# Scheme.net
KiCad netlist of a schematic drawn in EAGLE
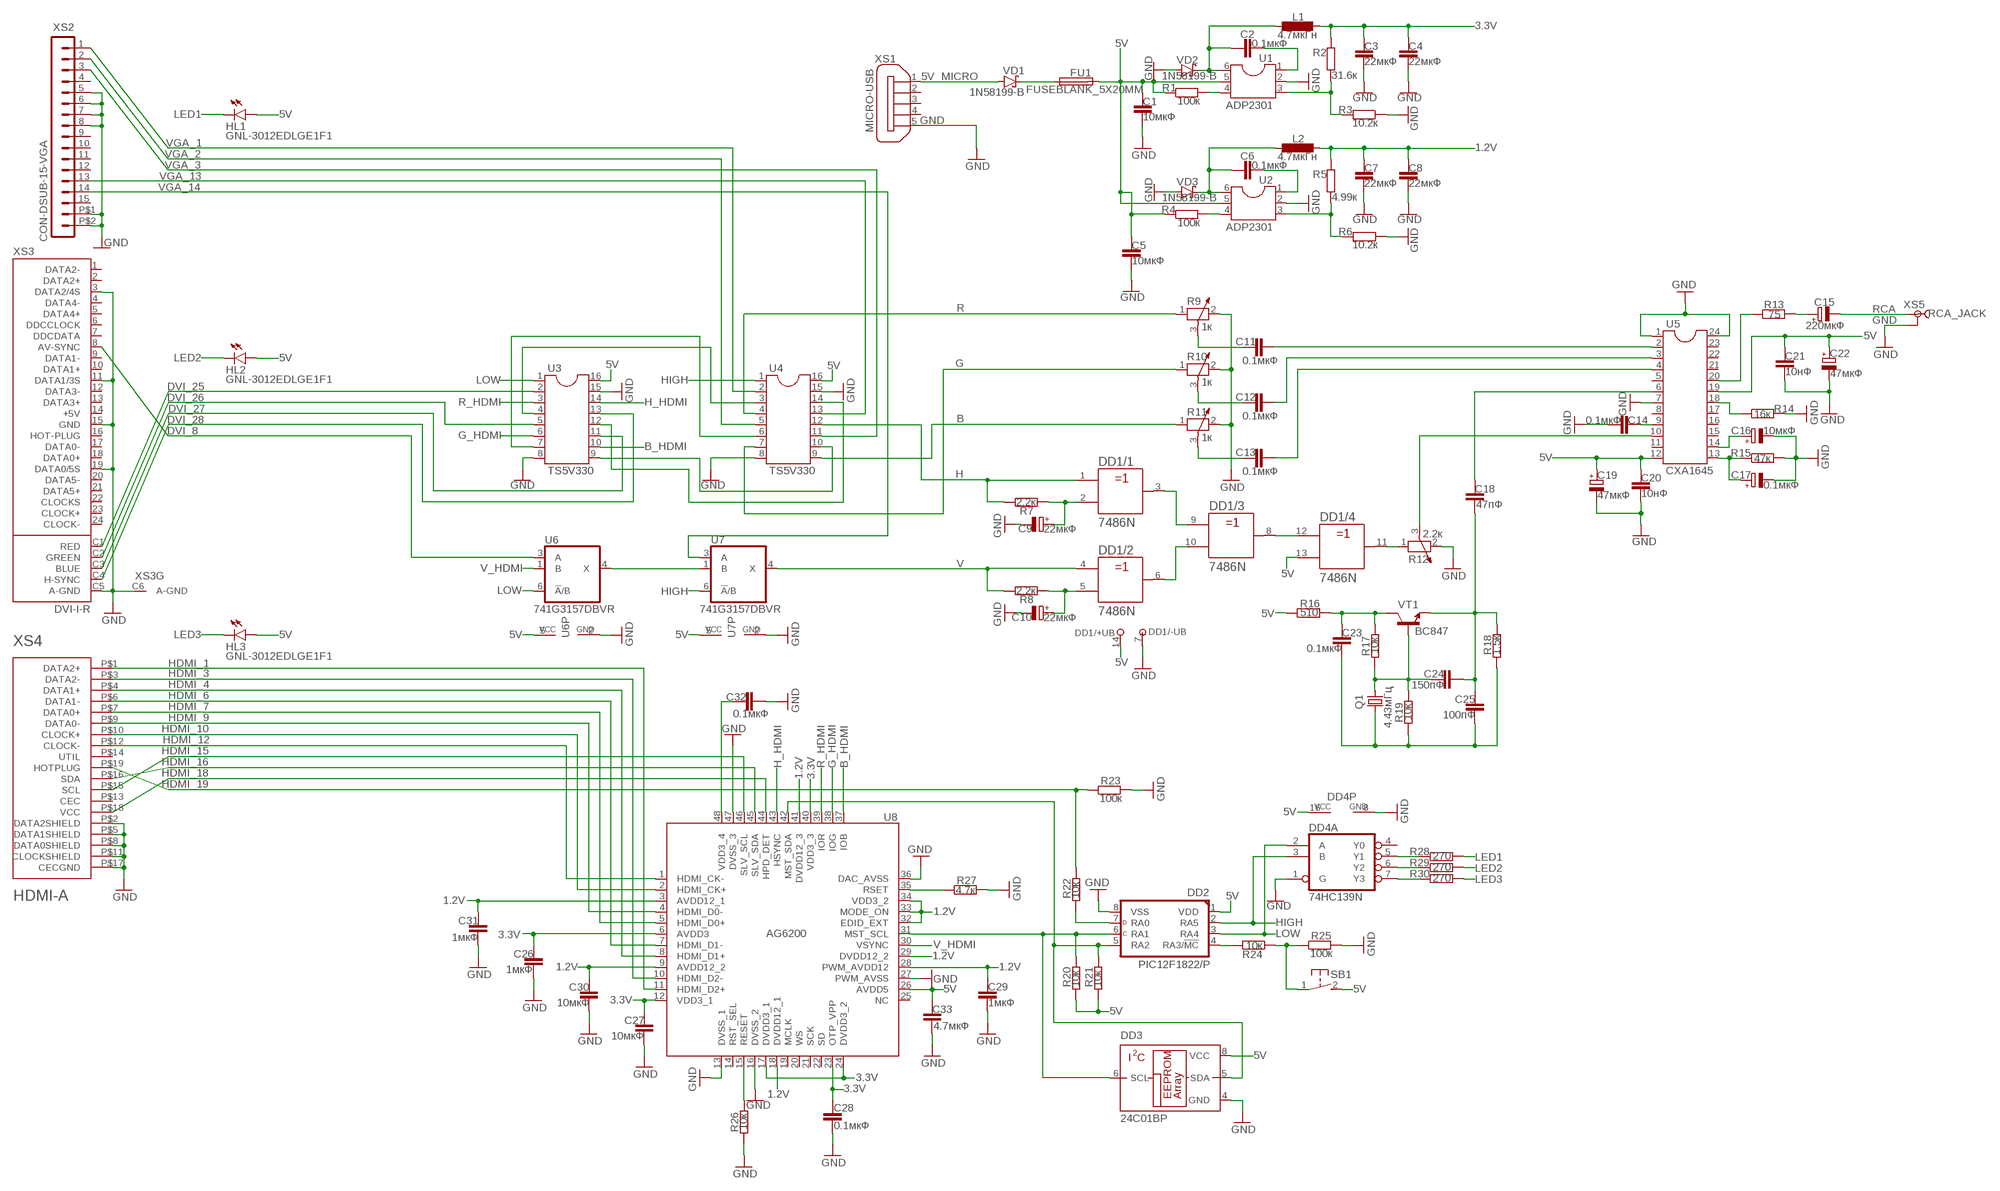
[diagram p0: schematic, sheet 1]

(export (version "E")
  (design (tool "Eeschema 10.0.6"))
  (components
    (comp (ref "C1")
      (value "10мкФ")
      (footprint "eagle-import:C0603")
      (libsource (lib "eagle-import") (part "C-EUC0603"))
    )
    (comp (ref "C2")
      (value "0.1мкФ")
      (footprint "eagle-import:C1206")
      (libsource (lib "eagle-import") (part "C-EUC1206"))
    )
    (comp (ref "C3")
      (value "22мкФ")
      (footprint "eagle-import:C1206")
      (libsource (lib "eagle-import") (part "C-EUC1206"))
    )
    (comp (ref "C4")
      (value "22мкФ")
      (footprint "eagle-import:C1206")
      (libsource (lib "eagle-import") (part "C-EUC1206"))
    )
    (comp (ref "C5")
      (value "10мкФ")
      (footprint "eagle-import:C0603")
      (libsource (lib "eagle-import") (part "C-EUC0603"))
    )
    (comp (ref "C6")
      (value "0.1мкФ")
      (footprint "eagle-import:C1206")
      (libsource (lib "eagle-import") (part "C-EUC1206"))
    )
    (comp (ref "C7")
      (value "22мкФ")
      (footprint "eagle-import:C1206")
      (libsource (lib "eagle-import") (part "C-EUC1206"))
    )
    (comp (ref "C8")
      (value "22мкФ")
      (footprint "eagle-import:C1206")
      (libsource (lib "eagle-import") (part "C-EUC1206"))
    )
    (comp (ref "C9")
      (value "22мкФ")
      (footprint "eagle-import:E2,5-6E")
      (libsource (lib "eagle-import") (part "CPOL-EUE2,5-6E"))
    )
    (comp (ref "C10")
      (value "22мкФ")
      (footprint "eagle-import:E2,5-6E")
      (libsource (lib "eagle-import") (part "CPOL-EUE2,5-6E"))
    )
    (comp (ref "C11")
      (value "0.1мкФ")
      (footprint "eagle-import:C1206")
      (libsource (lib "eagle-import") (part "C-EUC1206"))
    )
    (comp (ref "C12")
      (value "0.1мкФ")
      (footprint "eagle-import:C1206")
      (libsource (lib "eagle-import") (part "C-EUC1206"))
    )
    (comp (ref "C13")
      (value "0.1мкФ")
      (footprint "eagle-import:C1206")
      (libsource (lib "eagle-import") (part "C-EUC1206"))
    )
    (comp (ref "C14")
      (value "0.1мкФ")
      (footprint "eagle-import:C1206")
      (libsource (lib "eagle-import") (part "C-EUC1206"))
    )
    (comp (ref "C15")
      (value "220мкФ")
      (footprint "eagle-import:E2,5-6E")
      (libsource (lib "eagle-import") (part "CPOL-EUE2,5-6E"))
    )
    (comp (ref "C16")
      (value "10мкФ")
      (footprint "eagle-import:E2,5-6E")
      (libsource (lib "eagle-import") (part "CPOL-EUE2,5-6E"))
    )
    (comp (ref "C17")
      (value "0.1мкФ")
      (footprint "eagle-import:E2,5-6E")
      (libsource (lib "eagle-import") (part "CPOL-EUE2,5-6E"))
    )
    (comp (ref "C18")
      (value "47пФ")
      (footprint "eagle-import:C0603")
      (libsource (lib "eagle-import") (part "C-EUC0603"))
    )
    (comp (ref "C19")
      (value "47мкФ")
      (footprint "eagle-import:E2,5-6E")
      (libsource (lib "eagle-import") (part "CPOL-EUE2,5-6E"))
    )
    (comp (ref "C20")
      (value "10нФ")
      (footprint "eagle-import:C0603")
      (libsource (lib "eagle-import") (part "C-EUC0603"))
    )
    (comp (ref "C21")
      (value "10нФ")
      (footprint "eagle-import:C0603")
      (libsource (lib "eagle-import") (part "C-EUC0603"))
    )
    (comp (ref "C22")
      (value "47мкФ")
      (footprint "eagle-import:E2,5-6E")
      (libsource (lib "eagle-import") (part "CPOL-EUE2,5-6E"))
    )
    (comp (ref "C23")
      (value "0.1мкФ")
      (footprint "eagle-import:C1206")
      (libsource (lib "eagle-import") (part "C-EUC1206"))
    )
    (comp (ref "C24")
      (value "150пФ")
      (footprint "eagle-import:C0805")
      (libsource (lib "eagle-import") (part "C-EUC0805"))
    )
    (comp (ref "C25")
      (value "100пФ")
      (footprint "eagle-import:C0805")
      (libsource (lib "eagle-import") (part "C-EUC0805"))
    )
    (comp (ref "C26")
      (value "1мкФ")
      (footprint "eagle-import:C0603")
      (libsource (lib "eagle-import") (part "C-EUC0603"))
    )
    (comp (ref "C27")
      (value "10мкФ")
      (footprint "eagle-import:C0603")
      (libsource (lib "eagle-import") (part "C-EUC0603"))
    )
    (comp (ref "C28")
      (value "0.1мкФ")
      (footprint "eagle-import:C1206")
      (libsource (lib "eagle-import") (part "C-EUC1206"))
    )
    (comp (ref "C29")
      (value "1мкФ")
      (footprint "eagle-import:C0603")
      (libsource (lib "eagle-import") (part "C-EUC0603"))
    )
    (comp (ref "C30")
      (value "10мкФ")
      (footprint "eagle-import:C0603")
      (libsource (lib "eagle-import") (part "C-EUC0603"))
    )
    (comp (ref "C31")
      (value "1мкФ")
      (footprint "eagle-import:C0603")
      (libsource (lib "eagle-import") (part "C-EUC0603"))
    )
    (comp (ref "C32")
      (value "0.1мкФ")
      (footprint "eagle-import:C1206")
      (libsource (lib "eagle-import") (part "C-EUC1206"))
    )
    (comp (ref "C33")
      (value "4.7мкФ")
      (footprint "eagle-import:C0805")
      (libsource (lib "eagle-import") (part "C-EUC0805"))
    )
    (comp (ref "DD1")
      (value "7486N")
      (footprint "eagle-import:DIL14")
      (libsource (lib "eagle-import") (part "7486N"))
    )
    (comp (ref "DD2")
      (value "PIC12F1822/P")
      (footprint "eagle-import:DIL8-P")
      (libsource (lib "eagle-import") (part "PIC12F1822/P"))
    )
    (comp (ref "DD3")
      (value "24C01BP")
      (footprint "eagle-import:DIL8")
      (fields (field (name "MPN") "AT24C01B-PU"))
      (libsource (lib "eagle-import") (part "24C0P1B"))
    )
    (comp (ref "DD4")
      (value "74HC139N")
      (footprint "eagle-import:DIL16")
      (libsource (lib "eagle-import") (part "74139NHC"))
    )
    (comp (ref "FU1")
      (value "FUSEBLANK_5X20MM")
      (footprint "eagle-import:FUSE_HOLDER_5X20MM")
      (libsource (lib "eagle-import") (part "FUSEBLANK_5X20MM"))
    )
    (comp (ref "HL1")
      (value "GNL-3012EDLGE1F1")
      (footprint "eagle-import:PLCC2")
      (libsource (lib "eagle-import") (part "GNL-3012EDE1F1LG"))
    )
    (comp (ref "HL2")
      (value "GNL-3012EDLGE1F1")
      (footprint "eagle-import:PLCC2")
      (libsource (lib "eagle-import") (part "GNL-3012EDE1F1LG"))
    )
    (comp (ref "HL3")
      (value "GNL-3012EDLGE1F1")
      (footprint "eagle-import:PLCC2")
      (libsource (lib "eagle-import") (part "GNL-3012EDE1F1LG"))
    )
    (comp (ref "L1")
      (value "4.7мкГн")
      (footprint "eagle-import:PIS2816")
      (libsource (lib "eagle-import") (part "L-EUPIS2816"))
    )
    (comp (ref "L2")
      (value "4.7мкГн")
      (footprint "eagle-import:PIS2816")
      (libsource (lib "eagle-import") (part "L-EUPIS2816"))
    )
    (comp (ref "Q1")
      (value "4.43мГц")
      (footprint "eagle-import:HC49U-V")
      (libsource (lib "eagle-import") (part "CRYSTALHC49U-V"))
    )
    (comp (ref "R1")
      (value "100к")
      (footprint "eagle-import:R2512")
      (libsource (lib "eagle-import") (part "R-EU_R2512"))
    )
    (comp (ref "R2")
      (value "31.6к")
      (footprint "eagle-import:R0805")
      (libsource (lib "eagle-import") (part "R-EU_R0805"))
    )
    (comp (ref "R3")
      (value "10.2к")
      (footprint "eagle-import:R0805")
      (libsource (lib "eagle-import") (part "R-EU_R0805"))
    )
    (comp (ref "R4")
      (value "100к")
      (footprint "eagle-import:R2512")
      (libsource (lib "eagle-import") (part "R-EU_R2512"))
    )
    (comp (ref "R5")
      (value "4.99к")
      (footprint "eagle-import:R0805")
      (libsource (lib "eagle-import") (part "R-EU_R0805"))
    )
    (comp (ref "R6")
      (value "10.2к")
      (footprint "eagle-import:R0805")
      (libsource (lib "eagle-import") (part "R-EU_R0805"))
    )
    (comp (ref "R7")
      (value "2.2к")
      (footprint "eagle-import:R0402")
      (libsource (lib "eagle-import") (part "R-EU_R0402"))
    )
    (comp (ref "R8")
      (value "2.2к")
      (footprint "eagle-import:R0402")
      (libsource (lib "eagle-import") (part "R-EU_R0402"))
    )
    (comp (ref "R9")
      (value "1к")
      (footprint "eagle-import:PT-10")
      (libsource (lib "eagle-import") (part "POTENTIOMETER_PT-10"))
    )
    (comp (ref "R10")
      (value "1к")
      (footprint "eagle-import:PT-10")
      (libsource (lib "eagle-import") (part "POTENTIOMETER_PT-10"))
    )
    (comp (ref "R11")
      (value "1к")
      (footprint "eagle-import:PT-10")
      (libsource (lib "eagle-import") (part "POTENTIOMETER_PT-10"))
    )
    (comp (ref "R12")
      (value "2.2к")
      (footprint "eagle-import:PT-10")
      (libsource (lib "eagle-import") (part "POTENTIOMETER_PT-10"))
    )
    (comp (ref "R13")
      (value "75")
      (footprint "eagle-import:R0402")
      (libsource (lib "eagle-import") (part "R-EU_R0402"))
    )
    (comp (ref "R14")
      (value "16к")
      (footprint "eagle-import:R0402")
      (libsource (lib "eagle-import") (part "R-EU_R0402"))
    )
    (comp (ref "R15")
      (value "47к")
      (footprint "eagle-import:R0402")
      (libsource (lib "eagle-import") (part "R-EU_R0402"))
    )
    (comp (ref "R16")
      (value "510")
      (footprint "eagle-import:R0402")
      (libsource (lib "eagle-import") (part "R-EU_R0402"))
    )
    (comp (ref "R17")
      (value "10к")
      (footprint "eagle-import:R0805")
      (libsource (lib "eagle-import") (part "R-EU_R0805"))
    )
    (comp (ref "R18")
      (value "1.5к")
      (footprint "eagle-import:R0402")
      (libsource (lib "eagle-import") (part "R-EU_R0402"))
    )
    (comp (ref "R19")
      (value "10к")
      (footprint "eagle-import:R0805")
      (libsource (lib "eagle-import") (part "R-EU_R0805"))
    )
    (comp (ref "R20")
      (value "10к")
      (footprint "eagle-import:R0805")
      (libsource (lib "eagle-import") (part "R-EU_R0805"))
    )
    (comp (ref "R21")
      (value "10к")
      (footprint "eagle-import:R0805")
      (libsource (lib "eagle-import") (part "R-EU_R0805"))
    )
    (comp (ref "R22")
      (value "10к")
      (footprint "eagle-import:R0805")
      (libsource (lib "eagle-import") (part "R-EU_R0805"))
    )
    (comp (ref "R23")
      (value "100к")
      (footprint "eagle-import:R2512")
      (libsource (lib "eagle-import") (part "R-EU_R2512"))
    )
    (comp (ref "R24")
      (value "10к")
      (footprint "eagle-import:R0805")
      (libsource (lib "eagle-import") (part "R-EU_R0805"))
    )
    (comp (ref "R25")
      (value "100к")
      (footprint "eagle-import:R2512")
      (libsource (lib "eagle-import") (part "R-EU_R2512"))
    )
    (comp (ref "R26")
      (value "10к")
      (footprint "eagle-import:R0805")
      (libsource (lib "eagle-import") (part "R-EU_R0805"))
    )
    (comp (ref "R27")
      (value "4.7к")
      (footprint "eagle-import:R0402")
      (libsource (lib "eagle-import") (part "R-EU_R0402"))
    )
    (comp (ref "R28")
      (value "270")
      (footprint "eagle-import:R0402")
      (libsource (lib "eagle-import") (part "R-EU_R0402"))
    )
    (comp (ref "R29")
      (value "270")
      (footprint "eagle-import:R0402")
      (libsource (lib "eagle-import") (part "R-EU_R0402"))
    )
    (comp (ref "R30")
      (value "270")
      (footprint "eagle-import:R0402")
      (libsource (lib "eagle-import") (part "R-EU_R0402"))
    )
    (comp (ref "SB1")
      (value "31-XX")
      (footprint "eagle-import:B3F-31XX")
      (fields (field (name "MPN") "B3F-3100"))
      (libsource (lib "eagle-import") (part "31-XX"))
    )
    (comp (ref "U1")
      (value "ADP2301")
      (footprint "eagle-import:DIL06")
      (libsource (lib "eagle-import") (part "DIL6"))
    )
    (comp (ref "U2")
      (value "ADP2301")
      (footprint "eagle-import:DIL06")
      (libsource (lib "eagle-import") (part "DIL6"))
    )
    (comp (ref "U3")
      (value "TS5V330")
      (footprint "eagle-import:DIL16")
      (libsource (lib "eagle-import") (part "DIL16"))
    )
    (comp (ref "U4")
      (value "TS5V330")
      (footprint "eagle-import:DIL16")
      (libsource (lib "eagle-import") (part "DIL16"))
    )
    (comp (ref "U5")
      (value "CXA1645")
      (footprint "eagle-import:DIL24-4")
      (libsource (lib "eagle-import") (part "DIL24-4"))
    )
    (comp (ref "U6")
      (value "741G3157DBVR")
      (footprint "eagle-import:DBV_R-PDSO-G6")
      (libsource (lib "eagle-import") (part "741G3157DBVR"))
    )
    (comp (ref "U7")
      (value "741G3157DBVR")
      (footprint "eagle-import:DBV_R-PDSO-G6")
      (libsource (lib "eagle-import") (part "741G3157DBVR"))
    )
    (comp (ref "U8")
      (value "AG6200")
      (footprint "eagle-import:PLCC-48")
      (fields (field (name "MPN") "AD1953YSTZRL7"))
      (libsource (lib "eagle-import") (part "AG6200"))
    )
    (comp (ref "VD1")
      (value "1N58199-B")
      (footprint "eagle-import:DO41-7.6")
      (libsource (lib "eagle-import") (part "1N58199-B"))
    )
    (comp (ref "VD2")
      (value "1N58199-B")
      (footprint "eagle-import:DO41-7.6")
      (libsource (lib "eagle-import") (part "1N58199-B"))
    )
    (comp (ref "VD3")
      (value "1N58199-B")
      (footprint "eagle-import:DO41-7.6")
      (libsource (lib "eagle-import") (part "1N58199-B"))
    )
    (comp (ref "VT1")
      (value "BC847")
      (footprint "eagle-import:SOT23-BEC")
      (libsource (lib "eagle-import") (part "-NPN-SOT23-BECBC847"))
    )
    (comp (ref "XS1")
      (value "MICRO-USB")
      (footprint "eagle-import:ZX62D-B-5PA8")
      (fields (field (name "MF") "Hirose") (field (name "MPN") "ZX62D-B-5PA8"))
      (libsource (lib "eagle-import") (part "MICRO-USB"))
    )
    (comp (ref "XS2")
      (value "CON-DSUB-15-VGA")
      (footprint "eagle-import:181-015-212-171")
      (libsource (lib "eagle-import") (part "CON-DSUB-15-VGA"))
    )
    (comp (ref "XS3")
      (value "DVI-I-R")
      (footprint "eagle-import:DVI-I-R")
      (libsource (lib "eagle-import") (part "DVI-I-R"))
    )
    (comp (ref "XS4")
      (value "HDMI-A")
      (footprint "eagle-import:HDMI_A")
      (libsource (lib "eagle-import") (part "HDMI-A"))
    )
    (comp (ref "XS5")
      (value "RCA_JACK")
      (footprint "eagle-import:TOBU3")
      (fields (field (name "MF") "FARNELL") (field (name "MPN") "TOBU 3"))
      (libsource (lib "eagle-import") (part "RCA_JACK"))
    )
  )
  (nets
    (net (code "1") (name "/+5V") (class "Default")
      (node (ref "XS3") (pin "14") (pinfunction "+5V_14") (pintype "power_in"))
    )
    (net (code "2") (name "/1.2V") (class "Default")
      (node (ref "C29") (pin "1") (pinfunction "1_1") (pintype "passive"))
      (node (ref "C30") (pin "1") (pinfunction "1_1") (pintype "passive"))
      (node (ref "C31") (pin "1") (pinfunction "1_1") (pintype "passive"))
      (node (ref "C7") (pin "1") (pinfunction "1_1") (pintype "passive"))
      (node (ref "C8") (pin "1") (pinfunction "1_1") (pintype "passive"))
      (node (ref "L2") (pin "2") (pinfunction "2_2") (pintype "passive"))
      (node (ref "R5") (pin "2") (pinfunction "2_2") (pintype "passive"))
      (node (ref "U8") (pin "18") (pinfunction "DVDD12_1_18") (pintype "power_in"))
      (node (ref "U8") (pin "28") (pinfunction "PWM_AVDD12_28") (pintype "power_in"))
      (node (ref "U8") (pin "29") (pinfunction "DVDD12_2_29") (pintype "power_in"))
      (node (ref "U8") (pin "3") (pinfunction "AVDD12_1_3") (pintype "power_in"))
      (node (ref "U8") (pin "32") (pinfunction "EDID_EXT_32") (pintype "input"))
      (node (ref "U8") (pin "33") (pinfunction "MODE_ON_33") (pintype "input"))
      (node (ref "U8") (pin "34") (pinfunction "VDD3_2_34") (pintype "power_in"))
      (node (ref "U8") (pin "41") (pinfunction "DVDD12_3_41") (pintype "power_in"))
      (node (ref "U8") (pin "9") (pinfunction "AVDD12_2_9") (pintype "power_in"))
    )
    (net (code "3") (name "/3.3V") (class "Default")
      (node (ref "C26") (pin "1") (pinfunction "1_1") (pintype "passive"))
      (node (ref "C27") (pin "1") (pinfunction "1_1") (pintype "passive"))
      (node (ref "C28") (pin "1") (pinfunction "1_1") (pintype "passive"))
      (node (ref "C3") (pin "1") (pinfunction "1_1") (pintype "passive"))
      (node (ref "C4") (pin "1") (pinfunction "1_1") (pintype "passive"))
      (node (ref "L1") (pin "2") (pinfunction "2_2") (pintype "passive"))
      (node (ref "R2") (pin "2") (pinfunction "2_2") (pintype "passive"))
      (node (ref "U8") (pin "12") (pinfunction "VDD3_1_12") (pintype "power_in"))
      (node (ref "U8") (pin "17") (pinfunction "DVDD3_1_17") (pintype "power_in"))
      (node (ref "U8") (pin "23") (pinfunction "OTP_VPP_23") (pintype "power_in"))
      (node (ref "U8") (pin "24") (pinfunction "DVDD3_2_24") (pintype "power_in"))
      (node (ref "U8") (pin "40") (pinfunction "VDD3_3_40") (pintype "power_in"))
      (node (ref "U8") (pin "6") (pinfunction "AVDD3_6") (pintype "power_in"))
    )
    (net (code "4") (name "/5V") (class "Default")
      (node (ref "C1") (pin "1") (pinfunction "1_1") (pintype "passive"))
      (node (ref "C19") (pin "+") (pinfunction "+_+") (pintype "passive"))
      (node (ref "C20") (pin "1") (pinfunction "1_1") (pintype "passive"))
      (node (ref "C21") (pin "1") (pinfunction "1_1") (pintype "passive"))
      (node (ref "C22") (pin "+") (pinfunction "+_+") (pintype "passive"))
      (node (ref "C33") (pin "1") (pinfunction "1_1") (pintype "passive"))
      (node (ref "C5") (pin "1") (pinfunction "1_1") (pintype "passive"))
      (node (ref "DD1") (pin "13") (pinfunction "B_13") (pintype "input"))
      (node (ref "DD1") (pin "14") (pinfunction "+UB_14") (pintype "power_in"))
      (node (ref "DD2") (pin "1") (pinfunction "VDD_1") (pintype "passive"))
      (node (ref "DD3") (pin "8") (pinfunction "VCC_8") (pintype "power_in"))
      (node (ref "DD4") (pin "16") (pinfunction "VCC_16") (pintype "power_in"))
      (node (ref "FU1") (pin "2") (pinfunction "2_2") (pintype "passive"))
      (node (ref "HL1") (pin "A") (pinfunction "A_A") (pintype "passive"))
      (node (ref "HL2") (pin "A") (pinfunction "A_A") (pintype "passive"))
      (node (ref "HL3") (pin "A") (pinfunction "A_A") (pintype "passive"))
      (node (ref "R1") (pin "1") (pinfunction "1_1") (pintype "passive"))
      (node (ref "R16") (pin "1") (pinfunction "1_1") (pintype "passive"))
      (node (ref "R20") (pin "1") (pinfunction "1_1") (pintype "passive"))
      (node (ref "R21") (pin "1") (pinfunction "1_1") (pintype "passive"))
      (node (ref "R4") (pin "1") (pinfunction "1_1") (pintype "passive"))
      (node (ref "SB1") (pin "2") (pinfunction "S_2") (pintype "passive"))
      (node (ref "U1") (pin "5") (pinfunction "5_5") (pintype "passive"))
      (node (ref "U2") (pin "5") (pinfunction "5_5") (pintype "passive"))
      (node (ref "U3") (pin "16") (pinfunction "16_16") (pintype "passive"))
      (node (ref "U4") (pin "16") (pinfunction "16_16") (pintype "passive"))
      (node (ref "U5") (pin "12") (pinfunction "12_12") (pintype "passive"))
      (node (ref "U5") (pin "19") (pinfunction "19_19") (pintype "passive"))
      (node (ref "U6") (pin "5") (pinfunction "VCC_5") (pintype "power_in"))
      (node (ref "U7") (pin "5") (pinfunction "VCC_5") (pintype "power_in"))
      (node (ref "U8") (pin "26") (pinfunction "AVDD5_26") (pintype "power_in"))
    )
    (net (code "5") (name "/5V_MICRO") (class "Default")
      (node (ref "VD1") (pin "A") (pinfunction "A_A") (pintype "passive"))
      (node (ref "XS1") (pin "1") (pinfunction "1_1") (pintype "passive"))
    )
    (net (code "6") (name "/B") (class "Default")
      (node (ref "R11") (pin "1") (pinfunction "1_1") (pintype "passive"))
      (node (ref "U4") (pin "9") (pinfunction "9_9") (pintype "passive"))
    )
    (net (code "7") (name "/B_HDMI") (class "Default")
      (node (ref "U3") (pin "10") (pinfunction "10_10") (pintype "passive"))
      (node (ref "U8") (pin "37") (pinfunction "IOB_37") (pintype "output"))
    )
    (net (code "8") (name "/DVI_8") (class "Default")
      (node (ref "U6") (pin "3") (pinfunction "A_3") (pintype "bidirectional"))
      (node (ref "XS3") (pin "8") (pinfunction "AV-SYNC_8") (pintype "passive"))
    )
    (net (code "9") (name "/DVI_25") (class "Default")
      (node (ref "U3") (pin "2") (pinfunction "2_2") (pintype "passive"))
      (node (ref "XS3") (pin "C1") (pinfunction "RED_C1") (pintype "passive"))
    )
    (net (code "10") (name "/DVI_26") (class "Default")
      (node (ref "U3") (pin "5") (pinfunction "5_5") (pintype "passive"))
      (node (ref "XS3") (pin "C2") (pinfunction "GREEN_C2") (pintype "passive"))
    )
    (net (code "11") (name "/DVI_27") (class "Default")
      (node (ref "U3") (pin "11") (pinfunction "11_11") (pintype "passive"))
      (node (ref "XS3") (pin "C3") (pinfunction "BLUE_C3") (pintype "passive"))
    )
    (net (code "12") (name "/DVI_28") (class "Default")
      (node (ref "U3") (pin "13") (pinfunction "13_13") (pintype "passive"))
      (node (ref "XS3") (pin "C4") (pinfunction "H-SYNC_C4") (pintype "passive"))
    )
    (net (code "13") (name "/G") (class "Default")
      (node (ref "R10") (pin "1") (pinfunction "1_1") (pintype "passive"))
      (node (ref "U4") (pin "7") (pinfunction "7_7") (pintype "passive"))
    )
    (net (code "14") (name "/G_HDMI") (class "Default")
      (node (ref "U3") (pin "6") (pinfunction "6_6") (pintype "passive"))
      (node (ref "U8") (pin "38") (pinfunction "IOG_38") (pintype "output"))
    )
    (net (code "15") (name "/H") (class "Default")
      (node (ref "DD1") (pin "1") (pinfunction "A_1") (pintype "input"))
      (node (ref "R7") (pin "1") (pinfunction "1_1") (pintype "passive"))
      (node (ref "U4") (pin "12") (pinfunction "12_12") (pintype "passive"))
    )
    (net (code "16") (name "/HDMI_1") (class "Default")
      (node (ref "U8") (pin "11") (pinfunction "HDMI_D2+_11") (pintype "input"))
      (node (ref "XS4") (pin "P$1") (pinfunction "DATA2+_P$1") (pintype "bidirectional"))
    )
    (net (code "17") (name "/HDMI_3") (class "Default")
      (node (ref "U8") (pin "10") (pinfunction "HDMI_D2-_10") (pintype "input"))
      (node (ref "XS4") (pin "P$3") (pinfunction "DATA2-_P$3") (pintype "bidirectional"))
    )
    (net (code "18") (name "/HDMI_4") (class "Default")
      (node (ref "U8") (pin "8") (pinfunction "HDMI_D1+_8") (pintype "input"))
      (node (ref "XS4") (pin "P$4") (pinfunction "DATA1+_P$4") (pintype "bidirectional"))
    )
    (net (code "19") (name "/HDMI_6") (class "Default")
      (node (ref "U8") (pin "7") (pinfunction "HDMI_D1-_7") (pintype "input"))
      (node (ref "XS4") (pin "P$6") (pinfunction "DATA1-_P$6") (pintype "bidirectional"))
    )
    (net (code "20") (name "/HDMI_7") (class "Default")
      (node (ref "U8") (pin "5") (pinfunction "HDMI_D0+_5") (pintype "input"))
      (node (ref "XS4") (pin "P$7") (pinfunction "DATA0+_P$7") (pintype "bidirectional"))
    )
    (net (code "21") (name "/HDMI_9") (class "Default")
      (node (ref "U8") (pin "4") (pinfunction "HDMI_D0-_4") (pintype "input"))
      (node (ref "XS4") (pin "P$9") (pinfunction "DATA0-_P$9") (pintype "bidirectional"))
    )
    (net (code "22") (name "/HDMI_10") (class "Default")
      (node (ref "U8") (pin "2") (pinfunction "HDMI_CK+_2") (pintype "input"))
      (node (ref "XS4") (pin "P$10") (pinfunction "CLOCK+_P$10") (pintype "bidirectional"))
    )
    (net (code "23") (name "/HDMI_12") (class "Default")
      (node (ref "U8") (pin "1") (pinfunction "HDMI_CK-_1") (pintype "input"))
      (node (ref "XS4") (pin "P$12") (pinfunction "CLOCK-_P$12") (pintype "bidirectional"))
    )
    (net (code "24") (name "/HDMI_15") (class "Default")
      (node (ref "U8") (pin "46") (pinfunction "SLV_SCL_46") (pintype "bidirectional"))
      (node (ref "XS4") (pin "P$15") (pinfunction "SCL_P$15") (pintype "bidirectional"))
    )
    (net (code "25") (name "/HDMI_16") (class "Default")
      (node (ref "U8") (pin "45") (pinfunction "SLV_SDA_45") (pintype "bidirectional"))
      (node (ref "XS4") (pin "P$16") (pinfunction "SDA_P$16") (pintype "bidirectional"))
    )
    (net (code "26") (name "/HDMI_18") (class "Default")
      (node (ref "U8") (pin "44") (pinfunction "HPD_DET_44") (pintype "bidirectional"))
      (node (ref "XS4") (pin "P$18") (pinfunction "VCC_P$18") (pintype "bidirectional"))
    )
    (net (code "27") (name "/HDMI_19") (class "Default")
      (node (ref "R22") (pin "2") (pinfunction "2_2") (pintype "passive"))
      (node (ref "R23") (pin "1") (pinfunction "1_1") (pintype "passive"))
      (node (ref "XS4") (pin "P$19") (pinfunction "HOTPLUG_P$19") (pintype "bidirectional"))
    )
    (net (code "28") (name "/HIGH") (class "Default")
      (node (ref "DD2") (pin "2") (pinfunction "RA5_2") (pintype "bidirectional"))
      (node (ref "DD4") (pin "3") (pinfunction "B_3") (pintype "input"))
      (node (ref "U4") (pin "1") (pinfunction "1_1") (pintype "passive"))
      (node (ref "U7") (pin "6") (pinfunction "~{A}/B_6") (pintype "input"))
    )
    (net (code "29") (name "/H_HDMI") (class "Default")
      (node (ref "U3") (pin "14") (pinfunction "14_14") (pintype "passive"))
      (node (ref "U8") (pin "43") (pinfunction "HSYNC_43") (pintype "output"))
    )
    (net (code "30") (name "/LED1") (class "Default")
      (node (ref "HL1") (pin "C") (pinfunction "C_C") (pintype "passive"))
      (node (ref "R28") (pin "2") (pinfunction "2_2") (pintype "passive"))
    )
    (net (code "31") (name "/LED2") (class "Default")
      (node (ref "HL2") (pin "C") (pinfunction "C_C") (pintype "passive"))
      (node (ref "R29") (pin "2") (pinfunction "2_2") (pintype "passive"))
    )
    (net (code "32") (name "/LED3") (class "Default")
      (node (ref "HL3") (pin "C") (pinfunction "C_C") (pintype "passive"))
      (node (ref "R30") (pin "2") (pinfunction "2_2") (pintype "passive"))
    )
    (net (code "33") (name "/LOW") (class "Default")
      (node (ref "DD2") (pin "3") (pinfunction "RA4_3") (pintype "bidirectional"))
      (node (ref "DD4") (pin "2") (pinfunction "A_2") (pintype "input"))
      (node (ref "U3") (pin "1") (pinfunction "1_1") (pintype "passive"))
      (node (ref "U6") (pin "6") (pinfunction "~{A}/B_6") (pintype "input"))
    )
    (net (code "34") (name "/R") (class "Default")
      (node (ref "R9") (pin "1") (pinfunction "1_1") (pintype "passive"))
      (node (ref "U4") (pin "4") (pinfunction "4_4") (pintype "passive"))
    )
    (net (code "35") (name "/RCA") (class "Default")
      (node (ref "C15") (pin "-") (pinfunction "-_-") (pintype "passive"))
      (node (ref "XS5") (pin "1") (pinfunction "1_1") (pintype "passive"))
    )
    (net (code "36") (name "/R_HDMI") (class "Default")
      (node (ref "U3") (pin "3") (pinfunction "3_3") (pintype "passive"))
      (node (ref "U8") (pin "39") (pinfunction "IOR_39") (pintype "output"))
    )
    (net (code "37") (name "/V") (class "Default")
      (node (ref "DD1") (pin "4") (pinfunction "A_4") (pintype "input"))
      (node (ref "R8") (pin "1") (pinfunction "1_1") (pintype "passive"))
      (node (ref "U7") (pin "4") (pinfunction "X_4") (pintype "bidirectional"))
    )
    (net (code "38") (name "/VGA_1") (class "Default")
      (node (ref "U4") (pin "2") (pinfunction "2_2") (pintype "passive"))
      (node (ref "XS2") (pin "1") (pinfunction "1_1") (pintype "passive"))
    )
    (net (code "39") (name "/VGA_2") (class "Default")
      (node (ref "U4") (pin "5") (pinfunction "5_5") (pintype "passive"))
      (node (ref "XS2") (pin "2") (pinfunction "2_2") (pintype "passive"))
    )
    (net (code "40") (name "/VGA_3") (class "Default")
      (node (ref "U4") (pin "11") (pinfunction "11_11") (pintype "passive"))
      (node (ref "XS2") (pin "3") (pinfunction "3_3") (pintype "passive"))
    )
    (net (code "41") (name "/VGA_13") (class "Default")
      (node (ref "U4") (pin "13") (pinfunction "13_13") (pintype "passive"))
      (node (ref "XS2") (pin "13") (pinfunction "13_13") (pintype "passive"))
    )
    (net (code "42") (name "/VGA_14") (class "Default")
      (node (ref "U7") (pin "3") (pinfunction "A_3") (pintype "bidirectional"))
      (node (ref "XS2") (pin "14") (pinfunction "14_14") (pintype "passive"))
    )
    (net (code "43") (name "/V_HDMI") (class "Default")
      (node (ref "U6") (pin "1") (pinfunction "B_1") (pintype "bidirectional"))
      (node (ref "U8") (pin "30") (pinfunction "VSYNC_30") (pintype "output"))
    )
    (net (code "44") (name "GND") (class "Default")
      (node (ref "C1") (pin "2") (pinfunction "2_2") (pintype "passive"))
      (node (ref "C10") (pin "-") (pinfunction "-_-") (pintype "passive"))
      (node (ref "C14") (pin "2") (pinfunction "2_2") (pintype "passive"))
      (node (ref "C16") (pin "-") (pinfunction "-_-") (pintype "passive"))
      (node (ref "C17") (pin "-") (pinfunction "-_-") (pintype "passive"))
      (node (ref "C19") (pin "-") (pinfunction "-_-") (pintype "passive"))
      (node (ref "C20") (pin "2") (pinfunction "2_2") (pintype "passive"))
      (node (ref "C21") (pin "2") (pinfunction "2_2") (pintype "passive"))
      (node (ref "C22") (pin "-") (pinfunction "-_-") (pintype "passive"))
      (node (ref "C26") (pin "2") (pinfunction "2_2") (pintype "passive"))
      (node (ref "C27") (pin "2") (pinfunction "2_2") (pintype "passive"))
      (node (ref "C28") (pin "2") (pinfunction "2_2") (pintype "passive"))
      (node (ref "C29") (pin "2") (pinfunction "2_2") (pintype "passive"))
      (node (ref "C3") (pin "2") (pinfunction "2_2") (pintype "passive"))
      (node (ref "C30") (pin "2") (pinfunction "2_2") (pintype "passive"))
      (node (ref "C31") (pin "2") (pinfunction "2_2") (pintype "passive"))
      (node (ref "C32") (pin "2") (pinfunction "2_2") (pintype "passive"))
      (node (ref "C33") (pin "2") (pinfunction "2_2") (pintype "passive"))
      (node (ref "C4") (pin "2") (pinfunction "2_2") (pintype "passive"))
      (node (ref "C5") (pin "2") (pinfunction "2_2") (pintype "passive"))
      (node (ref "C7") (pin "2") (pinfunction "2_2") (pintype "passive"))
      (node (ref "C8") (pin "2") (pinfunction "2_2") (pintype "passive"))
      (node (ref "C9") (pin "-") (pinfunction "-_-") (pintype "passive"))
      (node (ref "DD1") (pin "7") (pinfunction "-UB_7") (pintype "power_in"))
      (node (ref "DD2") (pin "8") (pinfunction "VSS_8") (pintype "passive"))
      (node (ref "DD3") (pin "4") (pinfunction "GND_4") (pintype "power_in"))
      (node (ref "DD4") (pin "1") (pinfunction "G_1") (pintype "input"))
      (node (ref "DD4") (pin "8") (pinfunction "GND_8") (pintype "power_in"))
      (node (ref "R10") (pin "2") (pinfunction "2_2") (pintype "passive"))
      (node (ref "R11") (pin "2") (pinfunction "2_2") (pintype "passive"))
      (node (ref "R12") (pin "2") (pinfunction "2_2") (pintype "passive"))
      (node (ref "R14") (pin "2") (pinfunction "2_2") (pintype "passive"))
      (node (ref "R15") (pin "2") (pinfunction "2_2") (pintype "passive"))
      (node (ref "R23") (pin "2") (pinfunction "2_2") (pintype "passive"))
      (node (ref "R25") (pin "2") (pinfunction "2_2") (pintype "passive"))
      (node (ref "R26") (pin "1") (pinfunction "1_1") (pintype "passive"))
      (node (ref "R27") (pin "2") (pinfunction "2_2") (pintype "passive"))
      (node (ref "R3") (pin "1") (pinfunction "1_1") (pintype "passive"))
      (node (ref "R6") (pin "1") (pinfunction "1_1") (pintype "passive"))
      (node (ref "R9") (pin "2") (pinfunction "2_2") (pintype "passive"))
      (node (ref "U1") (pin "2") (pinfunction "2_2") (pintype "passive"))
      (node (ref "U2") (pin "2") (pinfunction "2_2") (pintype "passive"))
      (node (ref "U3") (pin "15") (pinfunction "15_15") (pintype "passive"))
      (node (ref "U3") (pin "8") (pinfunction "8_8") (pintype "passive"))
      (node (ref "U4") (pin "15") (pinfunction "15_15") (pintype "passive"))
      (node (ref "U4") (pin "8") (pinfunction "8_8") (pintype "passive"))
      (node (ref "U5") (pin "1") (pinfunction "1_1") (pintype "passive"))
      (node (ref "U5") (pin "24") (pinfunction "24_24") (pintype "passive"))
      (node (ref "U5") (pin "7") (pinfunction "7_7") (pintype "passive"))
      (node (ref "U6") (pin "2") (pinfunction "GND_2") (pintype "power_in"))
      (node (ref "U7") (pin "2") (pinfunction "GND_2") (pintype "power_in"))
      (node (ref "U8") (pin "13") (pinfunction "DVSS_1_13") (pintype "power_in"))
      (node (ref "U8") (pin "16") (pinfunction "DVSS_2_16") (pintype "power_in"))
      (node (ref "U8") (pin "27") (pinfunction "PWM_AVSS_27") (pintype "power_in"))
      (node (ref "U8") (pin "36") (pinfunction "DAC_AVSS_36") (pintype "power_in"))
      (node (ref "U8") (pin "47") (pinfunction "DVSS_3_47") (pintype "power_in"))
      (node (ref "VD2") (pin "A") (pinfunction "A_A") (pintype "passive"))
      (node (ref "VD3") (pin "A") (pinfunction "A_A") (pintype "passive"))
      (node (ref "XS1") (pin "5") (pinfunction "5_5") (pintype "passive"))
      (node (ref "XS2") (pin "5") (pinfunction "5_5") (pintype "passive"))
      (node (ref "XS2") (pin "6") (pinfunction "6_6") (pintype "passive"))
      (node (ref "XS2") (pin "7") (pinfunction "7_7") (pintype "passive"))
      (node (ref "XS2") (pin "8") (pinfunction "8_8") (pintype "passive"))
      (node (ref "XS2") (pin "P$1") (pinfunction "16_P$1") (pintype "passive"))
      (node (ref "XS2") (pin "P$2") (pinfunction "17_P$2") (pintype "passive"))
      (node (ref "XS3") (pin "11") (pinfunction "DATA1/3S_11") (pintype "passive"))
      (node (ref "XS3") (pin "15") (pinfunction "GND_15") (pintype "power_in"))
      (node (ref "XS3") (pin "19") (pinfunction "DATA0/5S_19") (pintype "passive"))
      (node (ref "XS3") (pin "3") (pinfunction "DATA2/4S_3") (pintype "passive"))
      (node (ref "XS3") (pin "C5") (pinfunction "A-GND_C5") (pintype "power_in"))
      (node (ref "XS3") (pin "C6") (pinfunction "A-GND_C6") (pintype "power_in"))
      (node (ref "XS4") (pin "P$11") (pinfunction "CLOCKSHIELD_P$11") (pintype "bidirectional"))
      (node (ref "XS4") (pin "P$17") (pinfunction "CECGND_P$17") (pintype "bidirectional"))
      (node (ref "XS4") (pin "P$2") (pinfunction "DATA2SHIELD_P$2") (pintype "bidirectional"))
      (node (ref "XS4") (pin "P$5") (pinfunction "DATA1SHIELD_P$5") (pintype "bidirectional"))
      (node (ref "XS4") (pin "P$8") (pinfunction "DATA0SHIELD_P$8") (pintype "bidirectional"))
      (node (ref "XS5") (pin "2") (pinfunction "2_2") (pintype "passive"))
      (node (ref "XS5") (pin "2@1") (pinfunction "2_2@1") (pintype "passive"))
      (node (ref "XS5") (pin "2@2") (pinfunction "2_2@2") (pintype "passive"))
    )
    (net (code "45") (name "Net-(C2-Pad1)") (class "Default")
      (node (ref "C2") (pin "1") (pinfunction "1_1") (pintype "passive"))
      (node (ref "L1") (pin "1") (pinfunction "1_1") (pintype "passive"))
      (node (ref "U1") (pin "6") (pinfunction "6_6") (pintype "passive"))
      (node (ref "VD2") (pin "C") (pinfunction "C_C") (pintype "passive"))
    )
    (net (code "46") (name "Net-(C2-Pad2)") (class "Default")
      (node (ref "C2") (pin "2") (pinfunction "2_2") (pintype "passive"))
      (node (ref "U1") (pin "1") (pinfunction "1_1") (pintype "passive"))
    )
    (net (code "47") (name "Net-(C6-Pad1)") (class "Default")
      (node (ref "C6") (pin "1") (pinfunction "1_1") (pintype "passive"))
      (node (ref "L2") (pin "1") (pinfunction "1_1") (pintype "passive"))
      (node (ref "U2") (pin "6") (pinfunction "6_6") (pintype "passive"))
      (node (ref "VD3") (pin "C") (pinfunction "C_C") (pintype "passive"))
    )
    (net (code "48") (name "Net-(C6-Pad2)") (class "Default")
      (node (ref "C6") (pin "2") (pinfunction "2_2") (pintype "passive"))
      (node (ref "U2") (pin "1") (pinfunction "1_1") (pintype "passive"))
    )
    (net (code "49") (name "Net-(C11-Pad1)") (class "Default")
      (node (ref "C11") (pin "1") (pinfunction "1_1") (pintype "passive"))
      (node (ref "R9") (pin "3") (pinfunction "3_3") (pintype "passive"))
    )
    (net (code "50") (name "Net-(C11-Pad2)") (class "Default")
      (node (ref "C11") (pin "2") (pinfunction "2_2") (pintype "passive"))
      (node (ref "U5") (pin "2") (pinfunction "2_2") (pintype "passive"))
    )
    (net (code "51") (name "Net-(C12-Pad1)") (class "Default")
      (node (ref "C12") (pin "1") (pinfunction "1_1") (pintype "passive"))
      (node (ref "R10") (pin "3") (pinfunction "3_3") (pintype "passive"))
    )
    (net (code "52") (name "Net-(C12-Pad2)") (class "Default")
      (node (ref "C12") (pin "2") (pinfunction "2_2") (pintype "passive"))
      (node (ref "U5") (pin "3") (pinfunction "3_3") (pintype "passive"))
    )
    (net (code "53") (name "Net-(C13-Pad1)") (class "Default")
      (node (ref "C13") (pin "1") (pinfunction "1_1") (pintype "passive"))
      (node (ref "R11") (pin "3") (pinfunction "3_3") (pintype "passive"))
    )
    (net (code "54") (name "Net-(C13-Pad2)") (class "Default")
      (node (ref "C13") (pin "2") (pinfunction "2_2") (pintype "passive"))
      (node (ref "U5") (pin "4") (pinfunction "4_4") (pintype "passive"))
    )
    (net (code "55") (name "Net-(C14-Pad1)") (class "Default")
      (node (ref "C14") (pin "1") (pinfunction "1_1") (pintype "passive"))
      (node (ref "U5") (pin "9") (pinfunction "9_9") (pintype "passive"))
    )
    (net (code "56") (name "Net-(C15-Pad+)") (class "Default")
      (node (ref "C15") (pin "+") (pinfunction "+_+") (pintype "passive"))
      (node (ref "R13") (pin "2") (pinfunction "2_2") (pintype "passive"))
    )
    (net (code "57") (name "Net-(C16-Pad+)") (class "Default")
      (node (ref "C16") (pin "+") (pinfunction "+_+") (pintype "passive"))
      (node (ref "U5") (pin "14") (pinfunction "14_14") (pintype "passive"))
    )
    (net (code "58") (name "Net-(C17-Pad+)") (class "Default")
      (node (ref "C17") (pin "+") (pinfunction "+_+") (pintype "passive"))
      (node (ref "R15") (pin "1") (pinfunction "1_1") (pintype "passive"))
      (node (ref "U5") (pin "13") (pinfunction "13_13") (pintype "passive"))
    )
    (net (code "59") (name "Net-(C18-Pad1)") (class "Default")
      (node (ref "C18") (pin "1") (pinfunction "1_1") (pintype "passive"))
      (node (ref "U5") (pin "6") (pinfunction "6_6") (pintype "passive"))
    )
    (net (code "60") (name "Net-(C18-Pad2)") (class "Default")
      (node (ref "C18") (pin "2") (pinfunction "2_2") (pintype "passive"))
      (node (ref "C24") (pin "2") (pinfunction "2_2") (pintype "passive"))
      (node (ref "C25") (pin "1") (pinfunction "1_1") (pintype "passive"))
      (node (ref "R18") (pin "2") (pinfunction "2_2") (pintype "passive"))
      (node (ref "VT1") (pin "E") (pinfunction "E_E") (pintype "passive"))
    )
    (net (code "61") (name "Net-(C23-Pad1)") (class "Default")
      (node (ref "C23") (pin "1") (pinfunction "1_1") (pintype "passive"))
      (node (ref "R16") (pin "2") (pinfunction "2_2") (pintype "passive"))
      (node (ref "R17") (pin "2") (pinfunction "2_2") (pintype "passive"))
      (node (ref "VT1") (pin "C") (pinfunction "C_C") (pintype "passive"))
    )
    (net (code "62") (name "Net-(C23-Pad2)") (class "Default")
      (node (ref "C23") (pin "2") (pinfunction "2_2") (pintype "passive"))
      (node (ref "C25") (pin "2") (pinfunction "2_2") (pintype "passive"))
      (node (ref "Q1") (pin "2") (pinfunction "2_2") (pintype "passive"))
      (node (ref "R18") (pin "1") (pinfunction "1_1") (pintype "passive"))
      (node (ref "R19") (pin "1") (pinfunction "1_1") (pintype "passive"))
    )
    (net (code "63") (name "Net-(C24-Pad1)") (class "Default")
      (node (ref "C24") (pin "1") (pinfunction "1_1") (pintype "passive"))
      (node (ref "Q1") (pin "1") (pinfunction "1_1") (pintype "passive"))
      (node (ref "R17") (pin "1") (pinfunction "1_1") (pintype "passive"))
      (node (ref "R19") (pin "2") (pinfunction "2_2") (pintype "passive"))
      (node (ref "VT1") (pin "B") (pinfunction "B_B") (pintype "passive"))
    )
    (net (code "64") (name "Net-(DD1C-B)") (class "Default")
      (node (ref "C9") (pin "+") (pinfunction "+_+") (pintype "passive"))
      (node (ref "DD1") (pin "2") (pinfunction "B_2") (pintype "input"))
      (node (ref "R7") (pin "2") (pinfunction "2_2") (pintype "passive"))
    )
    (net (code "65") (name "Net-(DD1C-Y)") (class "Default")
      (node (ref "DD1") (pin "3") (pinfunction "Y_3") (pintype "output"))
      (node (ref "DD1") (pin "9") (pinfunction "A_9") (pintype "input"))
    )
    (net (code "66") (name "Net-(DD1D-B)") (class "Default")
      (node (ref "C10") (pin "+") (pinfunction "+_+") (pintype "passive"))
      (node (ref "DD1") (pin "5") (pinfunction "B_5") (pintype "input"))
      (node (ref "R8") (pin "2") (pinfunction "2_2") (pintype "passive"))
    )
    (net (code "67") (name "Net-(DD1D-Y)") (class "Default")
      (node (ref "DD1") (pin "10") (pinfunction "B_10") (pintype "input"))
      (node (ref "DD1") (pin "6") (pinfunction "Y_6") (pintype "output"))
    )
    (net (code "68") (name "Net-(DD1E-Y)") (class "Default")
      (node (ref "DD1") (pin "12") (pinfunction "A_12") (pintype "input"))
      (node (ref "DD1") (pin "8") (pinfunction "Y_8") (pintype "output"))
    )
    (net (code "69") (name "Net-(DD1F-Y)") (class "Default")
      (node (ref "DD1") (pin "11") (pinfunction "Y_11") (pintype "output"))
      (node (ref "R12") (pin "1") (pinfunction "1_1") (pintype "passive"))
    )
    (net (code "70") (name "Net-(DD2-RA0)") (class "Default")
      (node (ref "DD2") (pin "7") (pinfunction "RA0_7") (pintype "bidirectional"))
      (node (ref "R22") (pin "1") (pinfunction "1_1") (pintype "passive"))
    )
    (net (code "71") (name "Net-(DD2-RA1)") (class "Default")
      (node (ref "DD2") (pin "6") (pinfunction "RA1_6") (pintype "bidirectional"))
      (node (ref "DD3") (pin "6") (pinfunction "SCL_6") (pintype "input"))
      (node (ref "R20") (pin "2") (pinfunction "2_2") (pintype "passive"))
      (node (ref "U8") (pin "31") (pinfunction "MST_SCL_31") (pintype "bidirectional"))
    )
    (net (code "72") (name "Net-(DD2-RA2)") (class "Default")
      (node (ref "DD2") (pin "5") (pinfunction "RA2_5") (pintype "bidirectional"))
      (node (ref "DD3") (pin "5") (pinfunction "SDA_5") (pintype "bidirectional"))
      (node (ref "R21") (pin "2") (pinfunction "2_2") (pintype "passive"))
      (node (ref "U8") (pin "42") (pinfunction "MST_SDA_42") (pintype "bidirectional"))
    )
    (net (code "73") (name "Net-(DD2-RA3{slash}~{MC})") (class "Default")
      (node (ref "DD2") (pin "4") (pinfunction "RA3/~{MC}_4") (pintype "bidirectional"))
      (node (ref "R24") (pin "2") (pinfunction "2_2") (pintype "passive"))
    )
    (net (code "74") (name "Net-(DD4A-Y1)") (class "Default")
      (node (ref "DD4") (pin "5") (pinfunction "Y1_5") (pintype "output"))
      (node (ref "R28") (pin "1") (pinfunction "1_1") (pintype "passive"))
    )
    (net (code "75") (name "Net-(DD4A-Y2)") (class "Default")
      (node (ref "DD4") (pin "6") (pinfunction "Y2_6") (pintype "output"))
      (node (ref "R29") (pin "1") (pinfunction "1_1") (pintype "passive"))
    )
    (net (code "76") (name "Net-(DD4A-Y3)") (class "Default")
      (node (ref "DD4") (pin "7") (pinfunction "Y3_7") (pintype "output"))
      (node (ref "R30") (pin "1") (pinfunction "1_1") (pintype "passive"))
    )
    (net (code "77") (name "Net-(FU1-Pad1)") (class "Default")
      (node (ref "FU1") (pin "1") (pinfunction "1_1") (pintype "passive"))
      (node (ref "VD1") (pin "C") (pinfunction "C_C") (pintype "passive"))
    )
    (net (code "78") (name "Net-(R1-Pad2)") (class "Default")
      (node (ref "R1") (pin "2") (pinfunction "2_2") (pintype "passive"))
      (node (ref "U1") (pin "4") (pinfunction "4_4") (pintype "passive"))
    )
    (net (code "79") (name "Net-(R2-Pad1)") (class "Default")
      (node (ref "R2") (pin "1") (pinfunction "1_1") (pintype "passive"))
      (node (ref "R3") (pin "2") (pinfunction "2_2") (pintype "passive"))
      (node (ref "U1") (pin "3") (pinfunction "3_3") (pintype "passive"))
    )
    (net (code "80") (name "Net-(R4-Pad2)") (class "Default")
      (node (ref "R4") (pin "2") (pinfunction "2_2") (pintype "passive"))
      (node (ref "U2") (pin "4") (pinfunction "4_4") (pintype "passive"))
    )
    (net (code "81") (name "Net-(R5-Pad1)") (class "Default")
      (node (ref "R5") (pin "1") (pinfunction "1_1") (pintype "passive"))
      (node (ref "R6") (pin "2") (pinfunction "2_2") (pintype "passive"))
      (node (ref "U2") (pin "3") (pinfunction "3_3") (pintype "passive"))
    )
    (net (code "82") (name "Net-(R12-Pad3)") (class "Default")
      (node (ref "R12") (pin "3") (pinfunction "3_3") (pintype "passive"))
      (node (ref "U5") (pin "10") (pinfunction "10_10") (pintype "passive"))
    )
    (net (code "83") (name "Net-(R13-Pad1)") (class "Default")
      (node (ref "R13") (pin "1") (pinfunction "1_1") (pintype "passive"))
      (node (ref "U5") (pin "20") (pinfunction "20_20") (pintype "passive"))
    )
    (net (code "84") (name "Net-(R14-Pad1)") (class "Default")
      (node (ref "R14") (pin "1") (pinfunction "1_1") (pintype "passive"))
      (node (ref "U5") (pin "18") (pinfunction "18_18") (pintype "passive"))
    )
    (net (code "85") (name "Net-(SB1-P)") (class "Default")
      (node (ref "R24") (pin "1") (pinfunction "1_1") (pintype "passive"))
      (node (ref "R25") (pin "1") (pinfunction "1_1") (pintype "passive"))
      (node (ref "SB1") (pin "1") (pinfunction "P_1") (pintype "passive"))
    )
    (net (code "86") (name "Net-(U3-Pad4)") (class "Default")
      (node (ref "U3") (pin "4") (pinfunction "4_4") (pintype "passive"))
      (node (ref "U4") (pin "3") (pinfunction "3_3") (pintype "passive"))
    )
    (net (code "87") (name "Net-(U3-Pad7)") (class "Default")
      (node (ref "U3") (pin "7") (pinfunction "7_7") (pintype "passive"))
      (node (ref "U4") (pin "6") (pinfunction "6_6") (pintype "passive"))
    )
    (net (code "88") (name "Net-(U3-Pad9)") (class "Default")
      (node (ref "U3") (pin "9") (pinfunction "9_9") (pintype "passive"))
      (node (ref "U4") (pin "10") (pinfunction "10_10") (pintype "passive"))
    )
    (net (code "89") (name "Net-(U3-Pad12)") (class "Default")
      (node (ref "U3") (pin "12") (pinfunction "12_12") (pintype "passive"))
      (node (ref "U4") (pin "14") (pinfunction "14_14") (pintype "passive"))
    )
    (net (code "90") (name "Net-(U6A-X)") (class "Default")
      (node (ref "U6") (pin "4") (pinfunction "X_4") (pintype "bidirectional"))
      (node (ref "U7") (pin "1") (pinfunction "B_1") (pintype "bidirectional"))
    )
    (net (code "91") (name "Net-(U8-RESET)") (class "Default")
      (node (ref "R26") (pin "2") (pinfunction "2_2") (pintype "passive"))
      (node (ref "U8") (pin "15") (pinfunction "RESET_15") (pintype "input"))
    )
    (net (code "92") (name "Net-(U8-RSET)") (class "Default")
      (node (ref "R27") (pin "1") (pinfunction "1_1") (pintype "passive"))
      (node (ref "U8") (pin "35") (pinfunction "RSET_35") (pintype "input"))
    )
    (net (code "93") (name "Net-(U8-VDD3_4)") (class "Default")
      (node (ref "C32") (pin "1") (pinfunction "1_1") (pintype "passive"))
      (node (ref "U8") (pin "48") (pinfunction "VDD3_4_48") (pintype "power_in"))
    )
    (net (code "94") (name "unconnected-(DD4A-Y0-Pad4)") (class "Default")
      (node (ref "DD4") (pin "4") (pinfunction "Y0_4") (pintype "output"))
    )
    (net (code "95") (name "unconnected-(U5-Pad5)") (class "Default")
      (node (ref "U5") (pin "5") (pinfunction "5_5") (pintype "passive"))
    )
    (net (code "96") (name "unconnected-(U5-Pad8)") (class "Default")
      (node (ref "U5") (pin "8") (pinfunction "8_8") (pintype "passive"))
    )
    (net (code "97") (name "unconnected-(U5-Pad11)") (class "Default")
      (node (ref "U5") (pin "11") (pinfunction "11_11") (pintype "passive"))
    )
    (net (code "98") (name "unconnected-(U5-Pad15)") (class "Default")
      (node (ref "U5") (pin "15") (pinfunction "15_15") (pintype "passive"))
    )
    (net (code "99") (name "unconnected-(U5-Pad16)") (class "Default")
      (node (ref "U5") (pin "16") (pinfunction "16_16") (pintype "passive"))
    )
    (net (code "100") (name "unconnected-(U5-Pad17)") (class "Default")
      (node (ref "U5") (pin "17") (pinfunction "17_17") (pintype "passive"))
    )
    (net (code "101") (name "unconnected-(U5-Pad21)") (class "Default")
      (node (ref "U5") (pin "21") (pinfunction "21_21") (pintype "passive"))
    )
    (net (code "102") (name "unconnected-(U5-Pad22)") (class "Default")
      (node (ref "U5") (pin "22") (pinfunction "22_22") (pintype "passive"))
    )
    (net (code "103") (name "unconnected-(U5-Pad23)") (class "Default")
      (node (ref "U5") (pin "23") (pinfunction "23_23") (pintype "passive"))
    )
    (net (code "104") (name "unconnected-(U8-MCLK-Pad19)") (class "Default")
      (node (ref "U8") (pin "19") (pinfunction "MCLK_19") (pintype "output"))
    )
    (net (code "105") (name "unconnected-(U8-NC-Pad25)") (class "Default")
      (node (ref "U8") (pin "25") (pinfunction "NC_25") (pintype "no_connect"))
    )
    (net (code "106") (name "unconnected-(U8-RST_SEL-Pad14)") (class "Default")
      (node (ref "U8") (pin "14") (pinfunction "RST_SEL_14") (pintype "input"))
    )
    (net (code "107") (name "unconnected-(U8-SCK-Pad21)") (class "Default")
      (node (ref "U8") (pin "21") (pinfunction "SCK_21") (pintype "output"))
    )
    (net (code "108") (name "unconnected-(U8-SD-Pad22)") (class "Default")
      (node (ref "U8") (pin "22") (pinfunction "SD_22") (pintype "output"))
    )
    (net (code "109") (name "unconnected-(U8-WS-Pad20)") (class "Default")
      (node (ref "U8") (pin "20") (pinfunction "WS_20") (pintype "output"))
    )
    (net (code "110") (name "unconnected-(XS1-Pad2)") (class "Default")
      (node (ref "XS1") (pin "2") (pinfunction "2_2") (pintype "passive"))
    )
    (net (code "111") (name "unconnected-(XS1-Pad3)") (class "Default")
      (node (ref "XS1") (pin "3") (pinfunction "3_3") (pintype "passive"))
    )
    (net (code "112") (name "unconnected-(XS1-Pad4)") (class "Default")
      (node (ref "XS1") (pin "4") (pinfunction "4_4") (pintype "passive"))
    )
    (net (code "113") (name "unconnected-(XS2-Pad4)") (class "Default")
      (node (ref "XS2") (pin "4") (pinfunction "4_4") (pintype "passive"))
    )
    (net (code "114") (name "unconnected-(XS2-Pad9)") (class "Default")
      (node (ref "XS2") (pin "9") (pinfunction "9_9") (pintype "passive"))
    )
    (net (code "115") (name "unconnected-(XS2-Pad10)") (class "Default")
      (node (ref "XS2") (pin "10") (pinfunction "10_10") (pintype "passive"))
    )
    (net (code "116") (name "unconnected-(XS2-Pad11)") (class "Default")
      (node (ref "XS2") (pin "11") (pinfunction "11_11") (pintype "passive"))
    )
    (net (code "117") (name "unconnected-(XS2-Pad12)") (class "Default")
      (node (ref "XS2") (pin "12") (pinfunction "12_12") (pintype "passive"))
    )
    (net (code "118") (name "unconnected-(XS2-Pad15)") (class "Default")
      (node (ref "XS2") (pin "15") (pinfunction "15_15") (pintype "passive"))
    )
    (net (code "119") (name "unconnected-(XS3B-CLOCK+-Pad23)") (class "Default")
      (node (ref "XS3") (pin "23") (pinfunction "CLOCK+_23") (pintype "passive"))
    )
    (net (code "120") (name "unconnected-(XS3B-CLOCK--Pad24)") (class "Default")
      (node (ref "XS3") (pin "24") (pinfunction "CLOCK-_24") (pintype "passive"))
    )
    (net (code "121") (name "unconnected-(XS3B-CLOCKS-Pad22)") (class "Default")
      (node (ref "XS3") (pin "22") (pinfunction "CLOCKS_22") (pintype "passive"))
    )
    (net (code "122") (name "unconnected-(XS3B-DATA0+-Pad18)") (class "Default")
      (node (ref "XS3") (pin "18") (pinfunction "DATA0+_18") (pintype "passive"))
    )
    (net (code "123") (name "unconnected-(XS3B-DATA0--Pad17)") (class "Default")
      (node (ref "XS3") (pin "17") (pinfunction "DATA0-_17") (pintype "passive"))
    )
    (net (code "124") (name "unconnected-(XS3B-DATA1+-Pad10)") (class "Default")
      (node (ref "XS3") (pin "10") (pinfunction "DATA1+_10") (pintype "passive"))
    )
    (net (code "125") (name "unconnected-(XS3B-DATA1--Pad9)") (class "Default")
      (node (ref "XS3") (pin "9") (pinfunction "DATA1-_9") (pintype "passive"))
    )
    (net (code "126") (name "unconnected-(XS3B-DATA2+-Pad2)") (class "Default")
      (node (ref "XS3") (pin "2") (pinfunction "DATA2+_2") (pintype "passive"))
    )
    (net (code "127") (name "unconnected-(XS3B-DATA2--Pad1)") (class "Default")
      (node (ref "XS3") (pin "1") (pinfunction "DATA2-_1") (pintype "passive"))
    )
    (net (code "128") (name "unconnected-(XS3B-DATA3+-Pad13)") (class "Default")
      (node (ref "XS3") (pin "13") (pinfunction "DATA3+_13") (pintype "passive"))
    )
    (net (code "129") (name "unconnected-(XS3B-DATA3--Pad12)") (class "Default")
      (node (ref "XS3") (pin "12") (pinfunction "DATA3-_12") (pintype "passive"))
    )
    (net (code "130") (name "unconnected-(XS3B-DATA4+-Pad5)") (class "Default")
      (node (ref "XS3") (pin "5") (pinfunction "DATA4+_5") (pintype "passive"))
    )
    (net (code "131") (name "unconnected-(XS3B-DATA4--Pad4)") (class "Default")
      (node (ref "XS3") (pin "4") (pinfunction "DATA4-_4") (pintype "passive"))
    )
    (net (code "132") (name "unconnected-(XS3B-DATA5+-Pad21)") (class "Default")
      (node (ref "XS3") (pin "21") (pinfunction "DATA5+_21") (pintype "passive"))
    )
    (net (code "133") (name "unconnected-(XS3B-DATA5--Pad20)") (class "Default")
      (node (ref "XS3") (pin "20") (pinfunction "DATA5-_20") (pintype "passive"))
    )
    (net (code "134") (name "unconnected-(XS3B-DDCCLOCK-Pad6)") (class "Default")
      (node (ref "XS3") (pin "6") (pinfunction "DDCCLOCK_6") (pintype "passive"))
    )
    (net (code "135") (name "unconnected-(XS3B-DDCDATA-Pad7)") (class "Default")
      (node (ref "XS3") (pin "7") (pinfunction "DDCDATA_7") (pintype "passive"))
    )
    (net (code "136") (name "unconnected-(XS3B-HOT-PLUG-Pad16)") (class "Default")
      (node (ref "XS3") (pin "16") (pinfunction "HOT-PLUG_16") (pintype "passive"))
    )
    (net (code "137") (name "unconnected-(XS4-CEC-PadP$13)") (class "Default")
      (node (ref "XS4") (pin "P$13") (pinfunction "CEC_P$13") (pintype "bidirectional"))
    )
    (net (code "138") (name "unconnected-(XS4-UTIL-PadP$14)") (class "Default")
      (node (ref "XS4") (pin "P$14") (pinfunction "UTIL_P$14") (pintype "bidirectional"))
    )
  )
)
